# CHIP_tzatziffy_v8.net
KiCad netlist of a schematic drawn in EAGLE
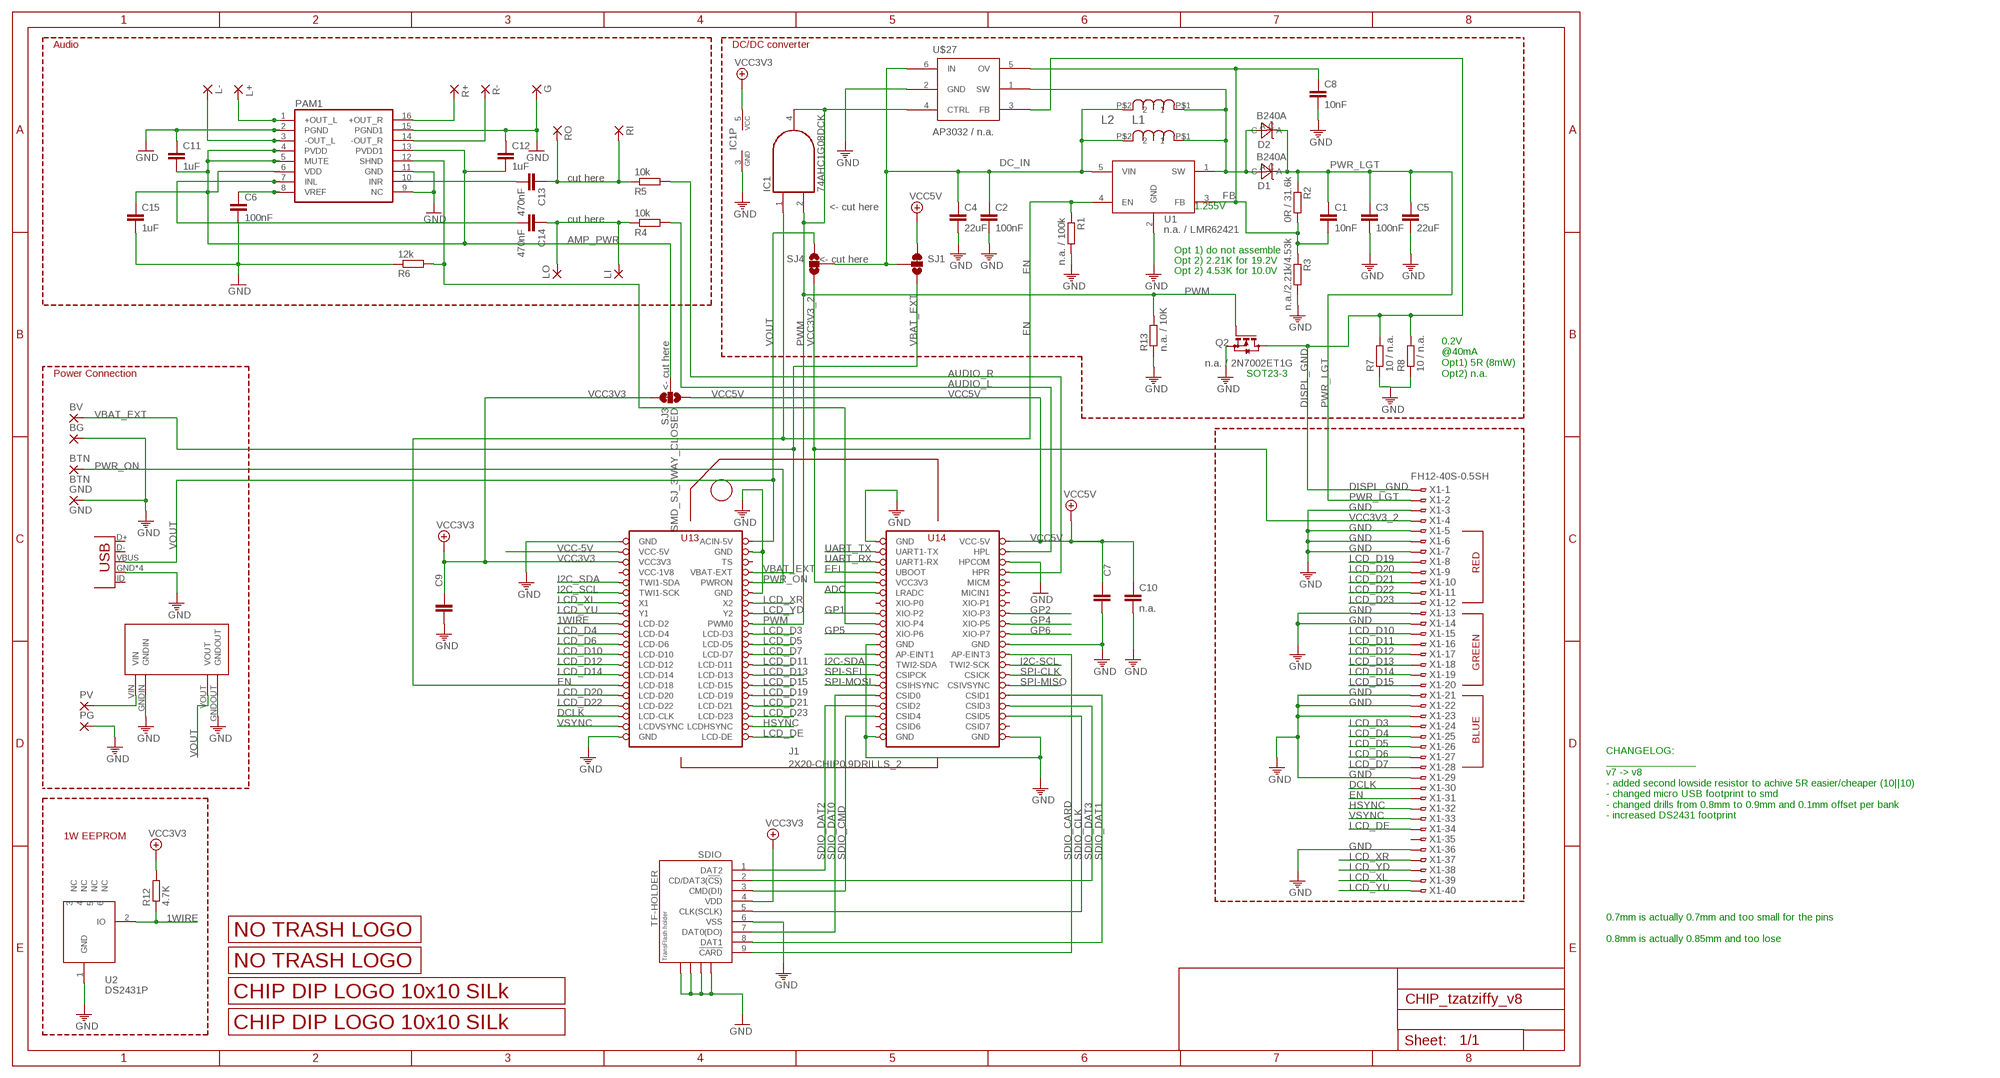
[diagram p0: schematic, sheet 1]

(export (version "E")
  (design (tool "Eeschema 10.0.6"))
  (components
    (comp (ref "BG")
      (value "1,6/0,8")
      (footprint "eagle-import:1,6_0,8")
      (libsource (lib "eagle-import") (part "1,6/0,8"))
    )
    (comp (ref "BTN")
      (value "BTN")
      (footprint "eagle-import:SMD1,27-2,54")
      (libsource (lib "eagle-import") (part "SMD2"))
    )
    (comp (ref "BV")
      (value "1,6/0,8")
      (footprint "eagle-import:1,6_0,8")
      (libsource (lib "eagle-import") (part "1,6/0,8"))
    )
    (comp (ref "C1")
      (value "10nF")
      (footprint "eagle-import:C0805")
      (libsource (lib "eagle-import") (part "C-EUC0805"))
    )
    (comp (ref "C2")
      (value "100nF")
      (footprint "eagle-import:C0805")
      (libsource (lib "eagle-import") (part "C-EUC0805"))
    )
    (comp (ref "C3")
      (value "100nF")
      (footprint "eagle-import:C0805")
      (libsource (lib "eagle-import") (part "C-EUC0805"))
    )
    (comp (ref "C4")
      (value "22uF")
      (footprint "eagle-import:C1206")
      (libsource (lib "eagle-import") (part "C-EUC1206"))
    )
    (comp (ref "C5")
      (value "22uF")
      (footprint "eagle-import:C1206")
      (libsource (lib "eagle-import") (part "C-EUC1206"))
    )
    (comp (ref "C6")
      (value "100nF")
      (footprint "eagle-import:C0805")
      (libsource (lib "eagle-import") (part "C-EUC0805"))
    )
    (comp (ref "C7")
      (value "n.a.")
      (footprint "eagle-import:C0805")
      (libsource (lib "eagle-import") (part "C-EUC0805"))
    )
    (comp (ref "C8")
      (value "10nF")
      (footprint "eagle-import:C0805")
      (libsource (lib "eagle-import") (part "C-EUC0805"))
    )
    (comp (ref "C9")
      (value "n.a.")
      (footprint "eagle-import:C0805")
      (libsource (lib "eagle-import") (part "C-EUC0805"))
    )
    (comp (ref "C10")
      (value "n.a.")
      (footprint "eagle-import:C0805")
      (libsource (lib "eagle-import") (part "C-EUC0805"))
    )
    (comp (ref "C11")
      (value "1uF")
      (footprint "eagle-import:C0805")
      (libsource (lib "eagle-import") (part "C-EUC0805"))
    )
    (comp (ref "C12")
      (value "1uF")
      (footprint "eagle-import:C0805")
      (libsource (lib "eagle-import") (part "C-EUC0805"))
    )
    (comp (ref "C13")
      (value "470nF")
      (footprint "eagle-import:C0805")
      (libsource (lib "eagle-import") (part "C-EUC0805"))
    )
    (comp (ref "C14")
      (value "470nF")
      (footprint "eagle-import:C0805")
      (libsource (lib "eagle-import") (part "C-EUC0805"))
    )
    (comp (ref "C15")
      (value "1uF")
      (footprint "eagle-import:C0805")
      (libsource (lib "eagle-import") (part "C-EUC0805"))
    )
    (comp (ref "D1")
      (value "B240A")
      (footprint "eagle-import:DO-214AC")
      (fields (field (name "MFG") "DIGIKEY") (field (name "VENDOR_PART_NUMBER") "B240A-13-F"))
      (libsource (lib "eagle-import") (part "DIODE_SCHTKY_B240"))
    )
    (comp (ref "D2")
      (value "B240A")
      (footprint "eagle-import:DO-214AC")
      (fields (field (name "MFG") "DIGIKEY") (field (name "VENDOR_PART_NUMBER") "B240A-13-F"))
      (libsource (lib "eagle-import") (part "DIODE_SCHTKY_B240"))
    )
    (comp (ref "G")
      (value "1,6/0,8")
      (footprint "eagle-import:1,6_0,8")
      (libsource (lib "eagle-import") (part "1,6/0,8"))
    )
    (comp (ref "GND")
      (value "GND")
      (footprint "eagle-import:SMD1,27-2,54")
      (libsource (lib "eagle-import") (part "SMD2"))
    )
    (comp (ref "IC1")
      (value "74AHC1G08DCK")
      (footprint "eagle-import:SC70-5")
      (libsource (lib "eagle-import") (part "741G08DCKAHC"))
    )
    (comp (ref "J1")
      (value "2X20-CHIP0.9DRILLS_2")
      (footprint "eagle-import:2X20CHIP_BANK_OFFSET_TH_0.9")
      (libsource (lib "eagle-import") (part "2X20-CHIP0.9DRILLS_2"))
    )
    (comp (ref "JP1")
      (value "USBMICRO_SMD")
      (footprint "eagle-import:USB-B-MICRO-SMD_V03")
      (libsource (lib "eagle-import") (part "USBMICRO_SMD"))
    )
    (comp (ref "L+")
      (value "1,6/0,8")
      (footprint "eagle-import:1,6_0,8")
      (libsource (lib "eagle-import") (part "1,6/0,8"))
    )
    (comp (ref "L-")
      (value "1,6/0,8")
      (footprint "eagle-import:1,6_0,8")
      (libsource (lib "eagle-import") (part "1,6/0,8"))
    )
    (comp (ref "L1")
      (value "SRN6045-100M")
      (footprint "eagle-import:SRN6045")
      (fields (field (name "MFG") "DIGIKEY"))
      (libsource (lib "eagle-import") (part "SRN6045-100M"))
    )
    (comp (ref "L2")
      (value "SRN6045-100M")
      (footprint "eagle-import:SRN6045")
      (fields (field (name "MFG") "DIGIKEY"))
      (libsource (lib "eagle-import") (part "SRN6045-100M"))
    )
    (comp (ref "LI")
      (value "1,6/0,8")
      (footprint "eagle-import:1,6_0,8")
      (libsource (lib "eagle-import") (part "1,6/0,8"))
    )
    (comp (ref "LO")
      (value "1,6/0,8")
      (footprint "eagle-import:1,6_0,8")
      (libsource (lib "eagle-import") (part "1,6/0,8"))
    )
    (comp (ref "PAM1")
      (value "PAM8403")
      (footprint "eagle-import:SOP-16")
      (libsource (lib "eagle-import") (part "PAM8403"))
    )
    (comp (ref "PG")
      (value "1,6/0,8")
      (footprint "eagle-import:1,6_0,8")
      (libsource (lib "eagle-import") (part "1,6/0,8"))
    )
    (comp (ref "PV")
      (value "1,6/0,8")
      (footprint "eagle-import:1,6_0,8")
      (libsource (lib "eagle-import") (part "1,6/0,8"))
    )
    (comp (ref "Q2")
      (value "n.a. / 2N7002ET1G")
      (footprint "eagle-import:SOT23")
      (libsource (lib "eagle-import") (part "BSS123"))
    )
    (comp (ref "R+")
      (value "1,6/0,8")
      (footprint "eagle-import:1,6_0,8")
      (libsource (lib "eagle-import") (part "1,6/0,8"))
    )
    (comp (ref "R-")
      (value "1,6/0,8")
      (footprint "eagle-import:1,6_0,8")
      (libsource (lib "eagle-import") (part "1,6/0,8"))
    )
    (comp (ref "R1")
      (value "n.a. / 100k")
      (footprint "eagle-import:M0805")
      (libsource (lib "eagle-import") (part "R-EU_M0805"))
    )
    (comp (ref "R2")
      (value "0R / 31.6k")
      (footprint "eagle-import:M0805")
      (libsource (lib "eagle-import") (part "R-EU_M0805"))
    )
    (comp (ref "R3")
      (value "n.a./2.21k/4.53k")
      (footprint "eagle-import:M0805")
      (libsource (lib "eagle-import") (part "R-EU_M0805"))
    )
    (comp (ref "R4")
      (value "10k")
      (footprint "eagle-import:R0805")
      (libsource (lib "eagle-import") (part "R-EU_R0805"))
    )
    (comp (ref "R5")
      (value "10k")
      (footprint "eagle-import:R0805")
      (libsource (lib "eagle-import") (part "R-EU_R0805"))
    )
    (comp (ref "R6")
      (value "12k")
      (footprint "eagle-import:R0805")
      (libsource (lib "eagle-import") (part "R-EU_R0805"))
    )
    (comp (ref "R7")
      (value "10 / n.a.")
      (footprint "eagle-import:M0805")
      (libsource (lib "eagle-import") (part "R-EU_M0805"))
    )
    (comp (ref "R8")
      (value "10 / n.a.")
      (footprint "eagle-import:M0805")
      (libsource (lib "eagle-import") (part "R-EU_M0805"))
    )
    (comp (ref "R12")
      (value "4.7K")
      (footprint "eagle-import:M0805")
      (libsource (lib "eagle-import") (part "R-EU_M0805"))
    )
    (comp (ref "R13")
      (value "n.a. / 10K")
      (footprint "eagle-import:M0805")
      (libsource (lib "eagle-import") (part "R-EU_M0805"))
    )
    (comp (ref "RI")
      (value "1,6/0,8")
      (footprint "eagle-import:1,6_0,8")
      (libsource (lib "eagle-import") (part "1,6/0,8"))
    )
    (comp (ref "RO")
      (value "1,6/0,8")
      (footprint "eagle-import:1,6_0,8")
      (libsource (lib "eagle-import") (part "1,6/0,8"))
    )
    (comp (ref "SDIO")
      (value "TF-HOLDER")
      (footprint "eagle-import:TF-PULL")
      (libsource (lib "eagle-import") (part "TF-HOLDER"))
    )
    (comp (ref "SJ1")
      (value "SMD_SJ_3WAY_CLOSED")
      (footprint "eagle-import:SMD_SJ_3WAY_CLOSED")
      (libsource (lib "eagle-import") (part "SMD_SJ_3WAY_CLOSED"))
    )
    (comp (ref "SJ3")
      (value "SMD_SJ_3WAY_CLOSED")
      (footprint "eagle-import:SMD_SJ_3WAY_CLOSED")
      (libsource (lib "eagle-import") (part "SMD_SJ_3WAY_CLOSED"))
    )
    (comp (ref "SJ4")
      (value "SMD_SJ_3WAY_OPENT")
      (footprint "eagle-import:SMD_SJ_3WAY_OPEN")
      (libsource (lib "eagle-import") (part "SMD_SJ_3WAY_OPENT"))
    )
    (comp (ref "U$2")
      (value "LOGO_10X10_SILK")
      (footprint "eagle-import:LOGO2_10X10_SILK")
      (libsource (lib "eagle-import") (part "LOGO_10X10_SILK"))
    )
    (comp (ref "U$3")
      (value "LOGO_NO_TRASHROHS")
      (footprint "eagle-import:LOGO_ROHS_SYM")
      (libsource (lib "eagle-import") (part "LOGO_NO_TRASHROHS"))
    )
    (comp (ref "U$4")
      (value "LOGO_NO_TRASHNO_TRASH")
      (footprint "eagle-import:LOGO_ROHS_NO_TRASH")
      (libsource (lib "eagle-import") (part "LOGO_NO_TRASHNO_TRASH"))
    )
    (comp (ref "U$5")
      (value "LOGO_10X10_SILK")
      (footprint "eagle-import:LOGO2_10X10_SILK")
      (libsource (lib "eagle-import") (part "LOGO_10X10_SILK"))
    )
    (comp (ref "U$10")
      (value "MP1584EN_FRAMELESS")
      (footprint "eagle-import:MP1584EN_FRAMELESS")
      (libsource (lib "eagle-import") (part "MP1584EN_FRAMELESS"))
    )
    (comp (ref "U$27")
      (value "AP3032 / n.a.")
      (footprint "eagle-import:SOT23-6")
      (libsource (lib "eagle-import") (part "AP3032"))
    )
    (comp (ref "U1")
      (value "n.a. / LMR62421")
      (footprint "eagle-import:SOT23-5")
      (fields (field (name "MFG") "DIGIKEY") (field (name "VENDOR_PART_NUMBER") "LMR62421XMFE/NOPB"))
      (libsource (lib "eagle-import") (part "LMR62421"))
    )
    (comp (ref "U2")
      (value "DS2431P")
      (footprint "eagle-import:TSOC6")
      (fields (field (name "MFG") "DIGIKEY") (field (name "VENDOR_PART_NUMBER") "DS2431P+T&R"))
      (libsource (lib "eagle-import") (part "DS2431P"))
    )
    (comp (ref "X1")
      (value "FH12-40S-0.5SH")
      (footprint "eagle-import:FH12-40S-0.5SH")
      (fields (field (name "MFG") "DIGIKEY") (field (name "VENDOR_PART_NUMBER") "FH12-40S-0.5SH(55)"))
      (libsource (lib "eagle-import") (part "FH12-40S-0.5SH"))
    )
  )
  (nets
    (net (code "1") (name "/1WIRE") (class "Default")
      (node (ref "J1") (pin "LCD-D2") (pinfunction "LCD-D2_LCD-D2") (pintype "passive"))
      (node (ref "R12") (pin "1") (pinfunction "1_1") (pintype "passive"))
      (node (ref "U2") (pin "2") (pinfunction "IO_2") (pintype "bidirectional"))
    )
    (net (code "2") (name "/ADC") (class "Default")
      (node (ref "J1") (pin "LRADC") (pinfunction "LRADC_LRADC") (pintype "passive"))
    )
    (net (code "3") (name "/AMP_PWR") (class "Default")
      (node (ref "C11") (pin "2") (pinfunction "2_2") (pintype "passive"))
      (node (ref "C12") (pin "2") (pinfunction "2_2") (pintype "passive"))
      (node (ref "C15") (pin "1") (pinfunction "1_1") (pintype "passive"))
      (node (ref "PAM1") (pin "13") (pinfunction "PVDD1_13") (pintype "output"))
      (node (ref "PAM1") (pin "4") (pinfunction "PVDD_4") (pintype "input"))
      (node (ref "PAM1") (pin "5") (pinfunction "MUTE_5") (pintype "input"))
      (node (ref "PAM1") (pin "6") (pinfunction "VDD_6") (pintype "input"))
      (node (ref "SJ3") (pin "2") (pinfunction "2_2") (pintype "passive"))
    )
    (net (code "4") (name "/AUDIO_L") (class "Default")
      (node (ref "J1") (pin "HPL") (pinfunction "HPL_HPL") (pintype "passive"))
      (node (ref "R4") (pin "2") (pinfunction "2_2") (pintype "passive"))
    )
    (net (code "5") (name "/AUDIO_R") (class "Default")
      (node (ref "J1") (pin "HPR") (pinfunction "HPR_HPR") (pintype "passive"))
      (node (ref "R5") (pin "2") (pinfunction "2_2") (pintype "passive"))
    )
    (net (code "6") (name "/DCLK") (class "Default")
      (node (ref "J1") (pin "LCD-CLK") (pinfunction "LCD-CLK_LCD-CLK") (pintype "passive"))
      (node (ref "X1") (pin "30") (pinfunction "1_30") (pintype "passive"))
    )
    (net (code "7") (name "/DC_IN") (class "Default")
      (node (ref "C2") (pin "1") (pinfunction "1_1") (pintype "passive"))
      (node (ref "C4") (pin "1") (pinfunction "1_1") (pintype "passive"))
      (node (ref "L1") (pin "P$2") (pinfunction "2_P$2") (pintype "passive"))
      (node (ref "L2") (pin "P$2") (pinfunction "2_P$2") (pintype "passive"))
      (node (ref "SJ1") (pin "2") (pinfunction "2_2") (pintype "passive"))
      (node (ref "SJ4") (pin "2") (pinfunction "2_2") (pintype "passive"))
      (node (ref "U$27") (pin "6") (pinfunction "IN_6") (pintype "power_in"))
      (node (ref "U1") (pin "5") (pinfunction "VIN_5") (pintype "bidirectional"))
    )
    (net (code "8") (name "/DISPL_GND") (class "Default")
      (node (ref "Q2") (pin "3") (pinfunction "D_3") (pintype "passive"))
      (node (ref "R7") (pin "2") (pinfunction "2_2") (pintype "passive"))
      (node (ref "R8") (pin "2") (pinfunction "2_2") (pintype "passive"))
      (node (ref "U$27") (pin "3") (pinfunction "FB_3") (pintype "passive"))
      (node (ref "X1") (pin "1") (pinfunction "1_1") (pintype "passive"))
    )
    (net (code "9") (name "/EN") (class "Default")
      (node (ref "IC1") (pin "1") (pinfunction "I0_1") (pintype "input"))
      (node (ref "J1") (pin "LCD-D18") (pinfunction "LCD-D18_LCD-D18") (pintype "passive"))
      (node (ref "R1") (pin "1") (pinfunction "1_1") (pintype "passive"))
      (node (ref "U1") (pin "4") (pinfunction "EN_4") (pintype "bidirectional"))
      (node (ref "X1") (pin "31") (pinfunction "1_31") (pintype "passive"))
    )
    (net (code "10") (name "/FB") (class "Default")
      (node (ref "C1") (pin "2") (pinfunction "2_2") (pintype "passive"))
      (node (ref "C8") (pin "1") (pinfunction "1_1") (pintype "passive"))
      (node (ref "R2") (pin "2") (pinfunction "2_2") (pintype "passive"))
      (node (ref "R3") (pin "1") (pinfunction "1_1") (pintype "passive"))
      (node (ref "U$27") (pin "5") (pinfunction "OV_5") (pintype "power_in"))
      (node (ref "U1") (pin "3") (pinfunction "FB_3") (pintype "bidirectional"))
    )
    (net (code "11") (name "/FEL") (class "Default")
      (node (ref "J1") (pin "FEL") (pinfunction "UBOOT_FEL") (pintype "passive"))
    )
    (net (code "12") (name "/GP1") (class "Default")
      (node (ref "J1") (pin "XIO-P2") (pinfunction "XIO-P2_XIO-P2") (pintype "passive"))
    )
    (net (code "13") (name "/GP2") (class "Default")
      (node (ref "J1") (pin "XIO-P3") (pinfunction "XIO-P3_XIO-P3") (pintype "passive"))
    )
    (net (code "14") (name "/GP4") (class "Default")
      (node (ref "J1") (pin "XIO-P5") (pinfunction "XIO-P5_XIO-P5") (pintype "passive"))
    )
    (net (code "15") (name "/GP5") (class "Default")
      (node (ref "J1") (pin "XIO-P6") (pinfunction "XIO-P6_XIO-P6") (pintype "passive"))
    )
    (net (code "16") (name "/GP6") (class "Default")
      (node (ref "J1") (pin "XIO-P7") (pinfunction "XIO-P7_XIO-P7") (pintype "passive"))
    )
    (net (code "17") (name "/HSYNC") (class "Default")
      (node (ref "J1") (pin "LCD-HSYNC") (pinfunction "LCDHSYNC_LCD-HSYNC") (pintype "passive"))
      (node (ref "X1") (pin "32") (pinfunction "1_32") (pintype "passive"))
    )
    (net (code "18") (name "/I2C-SCL") (class "Default")
      (node (ref "J1") (pin "TWI2-SCK") (pinfunction "TWI2-SCK_TWI2-SCK") (pintype "passive"))
    )
    (net (code "19") (name "/I2C-SDA") (class "Default")
      (node (ref "J1") (pin "TWI2-SDA") (pinfunction "TWI2-SDA_TWI2-SDA") (pintype "passive"))
    )
    (net (code "20") (name "/I2C_SCL") (class "Default")
      (node (ref "J1") (pin "TWI1-SCK") (pinfunction "TWI1-SCK_TWI1-SCK") (pintype "passive"))
    )
    (net (code "21") (name "/I2C_SDA") (class "Default")
      (node (ref "J1") (pin "TWI1-SDA") (pinfunction "TWI1-SDA_TWI1-SDA") (pintype "passive"))
    )
    (net (code "22") (name "/LCD_D3") (class "Default")
      (node (ref "J1") (pin "LCD-D3") (pinfunction "LCD-D3_LCD-D3") (pintype "passive"))
      (node (ref "X1") (pin "24") (pinfunction "1_24") (pintype "passive"))
    )
    (net (code "23") (name "/LCD_D4") (class "Default")
      (node (ref "J1") (pin "LCD-D4") (pinfunction "LCD-D4_LCD-D4") (pintype "passive"))
      (node (ref "X1") (pin "25") (pinfunction "1_25") (pintype "passive"))
    )
    (net (code "24") (name "/LCD_D5") (class "Default")
      (node (ref "J1") (pin "LCD-D5") (pinfunction "LCD-D5_LCD-D5") (pintype "passive"))
      (node (ref "X1") (pin "26") (pinfunction "1_26") (pintype "passive"))
    )
    (net (code "25") (name "/LCD_D6") (class "Default")
      (node (ref "J1") (pin "LCD-D6") (pinfunction "LCD-D6_LCD-D6") (pintype "passive"))
      (node (ref "X1") (pin "27") (pinfunction "1_27") (pintype "passive"))
    )
    (net (code "26") (name "/LCD_D7") (class "Default")
      (node (ref "J1") (pin "LCD-D7") (pinfunction "LCD-D7_LCD-D7") (pintype "passive"))
      (node (ref "X1") (pin "28") (pinfunction "1_28") (pintype "passive"))
    )
    (net (code "27") (name "/LCD_D10") (class "Default")
      (node (ref "J1") (pin "LCD-D10") (pinfunction "LCD-D10_LCD-D10") (pintype "passive"))
      (node (ref "X1") (pin "15") (pinfunction "1_15") (pintype "passive"))
    )
    (net (code "28") (name "/LCD_D11") (class "Default")
      (node (ref "J1") (pin "LCD-D11") (pinfunction "LCD-D11_LCD-D11") (pintype "passive"))
      (node (ref "X1") (pin "16") (pinfunction "1_16") (pintype "passive"))
    )
    (net (code "29") (name "/LCD_D12") (class "Default")
      (node (ref "J1") (pin "LCD-D12") (pinfunction "LCD-D12_LCD-D12") (pintype "passive"))
      (node (ref "X1") (pin "17") (pinfunction "1_17") (pintype "passive"))
    )
    (net (code "30") (name "/LCD_D13") (class "Default")
      (node (ref "J1") (pin "LCD-D13") (pinfunction "LCD-D13_LCD-D13") (pintype "passive"))
      (node (ref "X1") (pin "18") (pinfunction "1_18") (pintype "passive"))
    )
    (net (code "31") (name "/LCD_D14") (class "Default")
      (node (ref "J1") (pin "LCD-D14") (pinfunction "LCD-D14_LCD-D14") (pintype "passive"))
      (node (ref "X1") (pin "19") (pinfunction "1_19") (pintype "passive"))
    )
    (net (code "32") (name "/LCD_D15") (class "Default")
      (node (ref "J1") (pin "LCD-D15") (pinfunction "LCD-D15_LCD-D15") (pintype "passive"))
      (node (ref "X1") (pin "20") (pinfunction "1_20") (pintype "passive"))
    )
    (net (code "33") (name "/LCD_D19") (class "Default")
      (node (ref "J1") (pin "LCD-D19") (pinfunction "LCD-D19_LCD-D19") (pintype "passive"))
      (node (ref "X1") (pin "8") (pinfunction "1_8") (pintype "passive"))
    )
    (net (code "34") (name "/LCD_D20") (class "Default")
      (node (ref "J1") (pin "LCD-D20") (pinfunction "LCD-D20_LCD-D20") (pintype "passive"))
      (node (ref "X1") (pin "9") (pinfunction "1_9") (pintype "passive"))
    )
    (net (code "35") (name "/LCD_D21") (class "Default")
      (node (ref "J1") (pin "LCD-D21") (pinfunction "LCD-D21_LCD-D21") (pintype "passive"))
      (node (ref "X1") (pin "10") (pinfunction "1_10") (pintype "passive"))
    )
    (net (code "36") (name "/LCD_D22") (class "Default")
      (node (ref "J1") (pin "LCD-D22") (pinfunction "LCD-D22_LCD-D22") (pintype "passive"))
      (node (ref "X1") (pin "11") (pinfunction "1_11") (pintype "passive"))
    )
    (net (code "37") (name "/LCD_D23") (class "Default")
      (node (ref "J1") (pin "LCD-D23") (pinfunction "LCD-D23_LCD-D23") (pintype "passive"))
      (node (ref "X1") (pin "12") (pinfunction "1_12") (pintype "passive"))
    )
    (net (code "38") (name "/LCD_DE") (class "Default")
      (node (ref "J1") (pin "LCD-DE") (pinfunction "LCD-DE_LCD-DE") (pintype "passive"))
      (node (ref "X1") (pin "34") (pinfunction "1_34") (pintype "passive"))
    )
    (net (code "39") (name "/LCD_XL") (class "Default")
      (node (ref "J1") (pin "X1") (pinfunction "X1_X1") (pintype "passive"))
      (node (ref "X1") (pin "39") (pinfunction "1_39") (pintype "passive"))
    )
    (net (code "40") (name "/LCD_XR") (class "Default")
      (node (ref "J1") (pin "X2") (pinfunction "X2_X2") (pintype "passive"))
      (node (ref "X1") (pin "37") (pinfunction "1_37") (pintype "passive"))
    )
    (net (code "41") (name "/LCD_YD") (class "Default")
      (node (ref "J1") (pin "Y2") (pinfunction "Y2_Y2") (pintype "passive"))
      (node (ref "X1") (pin "38") (pinfunction "1_38") (pintype "passive"))
    )
    (net (code "42") (name "/LCD_YU") (class "Default")
      (node (ref "J1") (pin "Y1") (pinfunction "Y1_Y1") (pintype "passive"))
      (node (ref "X1") (pin "40") (pinfunction "1_40") (pintype "passive"))
    )
    (net (code "43") (name "/PWM") (class "Default")
      (node (ref "IC1") (pin "2") (pinfunction "I1_2") (pintype "input"))
      (node (ref "IC1") (pin "4") (pinfunction "O_4") (pintype "output"))
      (node (ref "J1") (pin "PWM0") (pinfunction "PWM0_PWM0") (pintype "passive"))
      (node (ref "Q2") (pin "1") (pinfunction "G_1") (pintype "passive"))
      (node (ref "R13") (pin "2") (pinfunction "2_2") (pintype "passive"))
      (node (ref "U$27") (pin "4") (pinfunction "CTRL_4") (pintype "input"))
    )
    (net (code "44") (name "/PWR_LGT") (class "Default")
      (node (ref "C1") (pin "1") (pinfunction "1_1") (pintype "passive"))
      (node (ref "C3") (pin "1") (pinfunction "1_1") (pintype "passive"))
      (node (ref "C5") (pin "1") (pinfunction "1_1") (pintype "passive"))
      (node (ref "D1") (pin "C") (pinfunction "C_C") (pintype "bidirectional"))
      (node (ref "D2") (pin "C") (pinfunction "C_C") (pintype "bidirectional"))
      (node (ref "R2") (pin "1") (pinfunction "1_1") (pintype "passive"))
      (node (ref "X1") (pin "2") (pinfunction "1_2") (pintype "passive"))
    )
    (net (code "45") (name "/PWR_ON") (class "Default")
      (node (ref "BTN") (pin "1") (pinfunction "P_1") (pintype "passive"))
      (node (ref "J1") (pin "PWRON") (pinfunction "PWRON_PWRON") (pintype "passive"))
    )
    (net (code "46") (name "/SDIO_CARD") (class "Default")
      (node (ref "J1") (pin "AP-EINT3") (pinfunction "AP-EINT3_AP-EINT3") (pintype "passive"))
      (node (ref "SDIO") (pin "9") (pinfunction "~{CARD}_9") (pintype "passive"))
    )
    (net (code "47") (name "/SDIO_CLK") (class "Default")
      (node (ref "J1") (pin "CSID5") (pinfunction "CSID5_CSID5") (pintype "passive"))
      (node (ref "SDIO") (pin "5") (pinfunction "CLK(SCLK)_5") (pintype "input"))
    )
    (net (code "48") (name "/SDIO_CMD") (class "Default")
      (node (ref "J1") (pin "CSID4") (pinfunction "CSID4_CSID4") (pintype "passive"))
      (node (ref "SDIO") (pin "3") (pinfunction "CMD(DI)_3") (pintype "bidirectional"))
    )
    (net (code "49") (name "/SDIO_DAT0") (class "Default")
      (node (ref "J1") (pin "CSID0") (pinfunction "CSID0_CSID0") (pintype "passive"))
      (node (ref "SDIO") (pin "7") (pinfunction "DAT0(DO)_7") (pintype "bidirectional"))
    )
    (net (code "50") (name "/SDIO_DAT1") (class "Default")
      (node (ref "J1") (pin "CSID1") (pinfunction "CSID1_CSID1") (pintype "passive"))
      (node (ref "SDIO") (pin "8") (pinfunction "DAT1_8") (pintype "bidirectional"))
    )
    (net (code "51") (name "/SDIO_DAT2") (class "Default")
      (node (ref "J1") (pin "CSID2") (pinfunction "CSID2_CSID2") (pintype "passive"))
      (node (ref "SDIO") (pin "1") (pinfunction "DAT2_1") (pintype "bidirectional"))
    )
    (net (code "52") (name "/SDIO_DAT3") (class "Default")
      (node (ref "J1") (pin "CSID3") (pinfunction "CSID3_CSID3") (pintype "passive"))
      (node (ref "SDIO") (pin "2") (pinfunction "CD/DAT3(~{CS})_2") (pintype "bidirectional"))
    )
    (net (code "53") (name "/SPI-CLK") (class "Default")
      (node (ref "J1") (pin "CSICK") (pinfunction "CSICK_CSICK") (pintype "passive"))
    )
    (net (code "54") (name "/SPI-MISO") (class "Default")
      (node (ref "J1") (pin "CSIVSYNC") (pinfunction "CSIVSYNC_CSIVSYNC") (pintype "passive"))
    )
    (net (code "55") (name "/SPI-MOSI") (class "Default")
      (node (ref "J1") (pin "CSIHSYNC") (pinfunction "CSIHSYNC_CSIHSYNC") (pintype "passive"))
    )
    (net (code "56") (name "/SPI-SEL") (class "Default")
      (node (ref "J1") (pin "CSIPCK") (pinfunction "CSIPCK_CSIPCK") (pintype "passive"))
    )
    (net (code "57") (name "/UART_RX") (class "Default")
      (node (ref "J1") (pin "UART1-RX") (pinfunction "UART1-RX_UART1-RX") (pintype "passive"))
    )
    (net (code "58") (name "/UART_TX") (class "Default")
      (node (ref "J1") (pin "UART1-TX") (pinfunction "UART1-TX_UART1-TX") (pintype "passive"))
    )
    (net (code "59") (name "/VBAT_EXT") (class "Default")
      (node (ref "BV") (pin "1") (pinfunction "P_1") (pintype "passive"))
      (node (ref "J1") (pin "BAT") (pinfunction "VBAT-EXT_BAT") (pintype "passive"))
      (node (ref "SJ1") (pin "3") (pinfunction "3_3") (pintype "passive"))
    )
    (net (code "60") (name "/VCC-1V8") (class "Default")
      (node (ref "J1") (pin "VCC1V8") (pinfunction "VCC-1V8_VCC1V8") (pintype "power_in"))
    )
    (net (code "61") (name "/VCC-5V") (class "Default")
      (node (ref "J1") (pin "VCC5V@0") (pinfunction "VCC-5V_VCC5V@0") (pintype "power_in"))
    )
    (net (code "62") (name "/VCC3V3_2") (class "Default")
      (node (ref "J1") (pin "VCC3V3@1") (pinfunction "VCC3V3_VCC3V3@1") (pintype "power_in"))
      (node (ref "SJ4") (pin "3") (pinfunction "3_3") (pintype "passive"))
      (node (ref "X1") (pin "4") (pinfunction "1_4") (pintype "passive"))
    )
    (net (code "63") (name "/VOUT") (class "Default")
      (node (ref "J1") (pin "CHG-IN") (pinfunction "ACIN-5V_CHG-IN") (pintype "passive"))
      (node (ref "JP1") (pin "VBUS") (pinfunction "VBUS_VBUS") (pintype "bidirectional"))
      (node (ref "SJ4") (pin "1") (pinfunction "1_1") (pintype "passive"))
      (node (ref "U$10") (pin "VOUT") (pinfunction "VOUT_VOUT") (pintype "power_in"))
    )
    (net (code "64") (name "/VSYNC") (class "Default")
      (node (ref "J1") (pin "LCD-VSYNC") (pinfunction "LCDVSYNC_LCD-VSYNC") (pintype "passive"))
      (node (ref "X1") (pin "33") (pinfunction "1_33") (pintype "passive"))
    )
    (net (code "65") (name "GND") (class "Default")
      (node (ref "BG") (pin "1") (pinfunction "P_1") (pintype "passive"))
      (node (ref "C10") (pin "2") (pinfunction "2_2") (pintype "passive"))
      (node (ref "C11") (pin "1") (pinfunction "1_1") (pintype "passive"))
      (node (ref "C12") (pin "1") (pinfunction "1_1") (pintype "passive"))
      (node (ref "C15") (pin "2") (pinfunction "2_2") (pintype "passive"))
      (node (ref "C2") (pin "2") (pinfunction "2_2") (pintype "passive"))
      (node (ref "C3") (pin "2") (pinfunction "2_2") (pintype "passive"))
      (node (ref "C4") (pin "2") (pinfunction "2_2") (pintype "passive"))
      (node (ref "C5") (pin "2") (pinfunction "2_2") (pintype "passive"))
      (node (ref "C6") (pin "2") (pinfunction "2_2") (pintype "passive"))
      (node (ref "C7") (pin "2") (pinfunction "2_2") (pintype "passive"))
      (node (ref "C8") (pin "2") (pinfunction "2_2") (pintype "passive"))
      (node (ref "C9") (pin "2") (pinfunction "2_2") (pintype "passive"))
      (node (ref "G") (pin "1") (pinfunction "P_1") (pintype "passive"))
      (node (ref "GND") (pin "1") (pinfunction "P_1") (pintype "passive"))
      (node (ref "IC1") (pin "3") (pinfunction "GND_3") (pintype "power_in"))
      (node (ref "J1") (pin "GND@1") (pinfunction "GND_GND@1") (pintype "power_in"))
      (node (ref "J1") (pin "GND@10") (pinfunction "GND_GND@10") (pintype "power_in"))
      (node (ref "J1") (pin "GND@2") (pinfunction "GND_GND@2") (pintype "power_in"))
      (node (ref "J1") (pin "GND@3") (pinfunction "GND_GND@3") (pintype "power_in"))
      (node (ref "J1") (pin "GND@4") (pinfunction "GND_GND@4") (pintype "power_in"))
      (node (ref "J1") (pin "GND@5") (pinfunction "GND_GND@5") (pintype "power_in"))
      (node (ref "J1") (pin "GND@6") (pinfunction "GND_GND@6") (pintype "power_in"))
      (node (ref "J1") (pin "GND@7") (pinfunction "GND_GND@7") (pintype "power_in"))
      (node (ref "J1") (pin "GND@8") (pinfunction "GND_GND@8") (pintype "power_in"))
      (node (ref "J1") (pin "HPCOM") (pinfunction "HPCOM_HPCOM") (pintype "passive"))
      (node (ref "JP1") (pin "GND") (pinfunction "GND_GND") (pintype "bidirectional"))
      (node (ref "JP1") (pin "SHIELD1") (pinfunction "GND_SHIELD1") (pintype "bidirectional"))
      (node (ref "JP1") (pin "SHIELD2") (pinfunction "GND_SHIELD2") (pintype "bidirectional"))
      (node (ref "JP1") (pin "SHIELD3") (pinfunction "GND_SHIELD3") (pintype "bidirectional"))
      (node (ref "PAM1") (pin "11") (pinfunction "GND_11") (pintype "output"))
      (node (ref "PAM1") (pin "15") (pinfunction "PGND1_15") (pintype "output"))
      (node (ref "PAM1") (pin "2") (pinfunction "PGND_2") (pintype "input"))
      (node (ref "PAM1") (pin "9") (pinfunction "NC_9") (pintype "output"))
      (node (ref "PG") (pin "1") (pinfunction "P_1") (pintype "passive"))
      (node (ref "Q2") (pin "2") (pinfunction "S_2") (pintype "passive"))
      (node (ref "R1") (pin "2") (pinfunction "2_2") (pintype "passive"))
      (node (ref "R13") (pin "1") (pinfunction "1_1") (pintype "passive"))
      (node (ref "R3") (pin "2") (pinfunction "2_2") (pintype "passive"))
      (node (ref "R6") (pin "1") (pinfunction "1_1") (pintype "passive"))
      (node (ref "R7") (pin "1") (pinfunction "1_1") (pintype "passive"))
      (node (ref "R8") (pin "1") (pinfunction "1_1") (pintype "passive"))
      (node (ref "SDIO") (pin "6") (pinfunction "VSS_6") (pintype "power_in"))
      (node (ref "SDIO") (pin "S1") (pinfunction "S1_S1") (pintype "passive"))
      (node (ref "SDIO") (pin "S2") (pinfunction "S2_S2") (pintype "passive"))
      (node (ref "SDIO") (pin "S3") (pinfunction "S3_S3") (pintype "passive"))
      (node (ref "SDIO") (pin "S4") (pinfunction "S4_S4") (pintype "passive"))
      (node (ref "U$10") (pin "GNDIN") (pinfunction "GNDIN_GNDIN") (pintype "power_in"))
      (node (ref "U$10") (pin "GNDOUT") (pinfunction "GNDOUT_GNDOUT") (pintype "power_in"))
      (node (ref "U$27") (pin "2") (pinfunction "GND_2") (pintype "power_in"))
      (node (ref "U1") (pin "2") (pinfunction "GND_2") (pintype "bidirectional"))
      (node (ref "U2") (pin "1") (pinfunction "GND_1") (pintype "bidirectional"))
      (node (ref "X1") (pin "13") (pinfunction "1_13") (pintype "passive"))
      (node (ref "X1") (pin "14") (pinfunction "1_14") (pintype "passive"))
      (node (ref "X1") (pin "21") (pinfunction "1_21") (pintype "passive"))
      (node (ref "X1") (pin "22") (pinfunction "1_22") (pintype "passive"))
      (node (ref "X1") (pin "23") (pinfunction "1_23") (pintype "passive"))
      (node (ref "X1") (pin "29") (pinfunction "1_29") (pintype "passive"))
      (node (ref "X1") (pin "3") (pinfunction "1_3") (pintype "passive"))
      (node (ref "X1") (pin "36") (pinfunction "1_36") (pintype "passive"))
      (node (ref "X1") (pin "5") (pinfunction "1_5") (pintype "passive"))
      (node (ref "X1") (pin "6") (pinfunction "1_6") (pintype "passive"))
      (node (ref "X1") (pin "7") (pinfunction "1_7") (pintype "passive"))
    )
    (net (code "66") (name "Net-(L+-P)") (class "Default")
      (node (ref "L+") (pin "1") (pinfunction "P_1") (pintype "passive"))
      (node (ref "PAM1") (pin "1") (pinfunction "+OUT_L_1") (pintype "input"))
    )
    (net (code "67") (name "Net-(L--P)") (class "Default")
      (node (ref "L-") (pin "1") (pinfunction "P_1") (pintype "passive"))
      (node (ref "PAM1") (pin "3") (pinfunction "-OUT_L_3") (pintype "input"))
    )
    (net (code "68") (name "Net-(L1-1)") (class "Default")
      (node (ref "D1") (pin "A") (pinfunction "A_A") (pintype "bidirectional"))
      (node (ref "D2") (pin "A") (pinfunction "A_A") (pintype "bidirectional"))
      (node (ref "L1") (pin "P$1") (pinfunction "1_P$1") (pintype "passive"))
      (node (ref "L2") (pin "P$1") (pinfunction "1_P$1") (pintype "passive"))
      (node (ref "U$27") (pin "1") (pinfunction "SW_1") (pintype "power_in"))
      (node (ref "U1") (pin "1") (pinfunction "SW_1") (pintype "bidirectional"))
    )
    (net (code "69") (name "Net-(LI-P)") (class "Default")
      (node (ref "C14") (pin "1") (pinfunction "1_1") (pintype "passive"))
      (node (ref "LI") (pin "1") (pinfunction "P_1") (pintype "passive"))
      (node (ref "LO") (pin "1") (pinfunction "P_1") (pintype "passive"))
      (node (ref "R4") (pin "1") (pinfunction "1_1") (pintype "passive"))
    )
    (net (code "70") (name "Net-(PAM1-+OUT_R)") (class "Default")
      (node (ref "PAM1") (pin "16") (pinfunction "+OUT_R_16") (pintype "output"))
      (node (ref "R+") (pin "1") (pinfunction "P_1") (pintype "passive"))
    )
    (net (code "71") (name "Net-(PAM1--OUT_R)") (class "Default")
      (node (ref "PAM1") (pin "14") (pinfunction "-OUT_R_14") (pintype "output"))
      (node (ref "R-") (pin "1") (pinfunction "P_1") (pintype "passive"))
    )
    (net (code "72") (name "Net-(PAM1-INL)") (class "Default")
      (node (ref "C14") (pin "2") (pinfunction "2_2") (pintype "passive"))
      (node (ref "PAM1") (pin "7") (pinfunction "INL_7") (pintype "input"))
    )
    (net (code "73") (name "Net-(PAM1-INR)") (class "Default")
      (node (ref "C13") (pin "2") (pinfunction "2_2") (pintype "passive"))
      (node (ref "PAM1") (pin "10") (pinfunction "INR_10") (pintype "output"))
    )
    (net (code "74") (name "Net-(PAM1-SHND)") (class "Default")
      (node (ref "J1") (pin "XIO-P4") (pinfunction "XIO-P4_XIO-P4") (pintype "passive"))
      (node (ref "PAM1") (pin "12") (pinfunction "SHND_12") (pintype "output"))
      (node (ref "R6") (pin "2") (pinfunction "2_2") (pintype "passive"))
    )
    (net (code "75") (name "Net-(PAM1-VREF)") (class "Default")
      (node (ref "C6") (pin "1") (pinfunction "1_1") (pintype "passive"))
      (node (ref "PAM1") (pin "8") (pinfunction "VREF_8") (pintype "input"))
    )
    (net (code "76") (name "Net-(PV-P)") (class "Default")
      (node (ref "PV") (pin "1") (pinfunction "P_1") (pintype "passive"))
      (node (ref "U$10") (pin "VIN") (pinfunction "VIN_VIN") (pintype "power_in"))
    )
    (net (code "77") (name "Net-(RI-P)") (class "Default")
      (node (ref "C13") (pin "1") (pinfunction "1_1") (pintype "passive"))
      (node (ref "R5") (pin "1") (pinfunction "1_1") (pintype "passive"))
      (node (ref "RI") (pin "1") (pinfunction "P_1") (pintype "passive"))
      (node (ref "RO") (pin "1") (pinfunction "P_1") (pintype "passive"))
    )
    (net (code "78") (name "VCC3V3") (class "Default")
      (node (ref "C9") (pin "1") (pinfunction "1_1") (pintype "passive"))
      (node (ref "IC1") (pin "5") (pinfunction "VCC_5") (pintype "power_in"))
      (node (ref "J1") (pin "VCC3V3") (pinfunction "VCC3V3_VCC3V3") (pintype "power_in"))
      (node (ref "R12") (pin "2") (pinfunction "2_2") (pintype "passive"))
      (node (ref "SDIO") (pin "4") (pinfunction "VDD_4") (pintype "power_in"))
      (node (ref "SJ3") (pin "1") (pinfunction "1_1") (pintype "passive"))
    )
    (net (code "79") (name "VCC5V") (class "Default")
      (node (ref "C10") (pin "1") (pinfunction "1_1") (pintype "passive"))
      (node (ref "C7") (pin "1") (pinfunction "1_1") (pintype "passive"))
      (node (ref "J1") (pin "VCC5V@1") (pinfunction "VCC-5V_VCC5V@1") (pintype "power_in"))
      (node (ref "SJ1") (pin "1") (pinfunction "1_1") (pintype "passive"))
      (node (ref "SJ3") (pin "3") (pinfunction "3_3") (pintype "passive"))
    )
    (net (code "80") (name "unconnected-(J1-PadAP-EINT1)") (class "Default")
      (node (ref "J1") (pin "AP-EINT1") (pinfunction "AP-EINT1_AP-EINT1") (pintype "passive"))
    )
    (net (code "81") (name "unconnected-(J1-PadCSID6)") (class "Default")
      (node (ref "J1") (pin "CSID6") (pinfunction "CSID6_CSID6") (pintype "passive"))
    )
    (net (code "82") (name "unconnected-(J1-PadCSID7)") (class "Default")
      (node (ref "J1") (pin "CSID7") (pinfunction "CSID7_CSID7") (pintype "passive"))
    )
    (net (code "83") (name "unconnected-(J1-PadMICIN1)") (class "Default")
      (node (ref "J1") (pin "MICIN1") (pinfunction "MICIN1_MICIN1") (pintype "passive"))
    )
    (net (code "84") (name "unconnected-(J1-PadMICM)") (class "Default")
      (node (ref "J1") (pin "MICM") (pinfunction "MICM_MICM") (pintype "passive"))
    )
    (net (code "85") (name "unconnected-(J1-PadTS)") (class "Default")
      (node (ref "J1") (pin "TS") (pinfunction "TS_TS") (pintype "passive"))
    )
    (net (code "86") (name "unconnected-(J1-PadXIO-P0)") (class "Default")
      (node (ref "J1") (pin "XIO-P0") (pinfunction "XIO-P0_XIO-P0") (pintype "passive"))
    )
    (net (code "87") (name "unconnected-(J1-PadXIO-P1)") (class "Default")
      (node (ref "J1") (pin "XIO-P1") (pinfunction "XIO-P1_XIO-P1") (pintype "passive"))
    )
    (net (code "88") (name "unconnected-(JP1-PadD+)") (class "Default")
      (node (ref "JP1") (pin "D+") (pinfunction "D+_D+") (pintype "bidirectional"))
    )
    (net (code "89") (name "unconnected-(JP1-PadD-)") (class "Default")
      (node (ref "JP1") (pin "D-") (pinfunction "D-_D-") (pintype "bidirectional"))
    )
    (net (code "90") (name "unconnected-(JP1-PadID)") (class "Default")
      (node (ref "JP1") (pin "ID") (pinfunction "ID_ID") (pintype "bidirectional"))
    )
    (net (code "91") (name "unconnected-(U2-NC-Pad3)") (class "Default")
      (node (ref "U2") (pin "3") (pinfunction "NC_3") (pintype "bidirectional"))
    )
    (net (code "92") (name "unconnected-(U2-NC-Pad4)") (class "Default")
      (node (ref "U2") (pin "4") (pinfunction "NC_4") (pintype "bidirectional"))
    )
    (net (code "93") (name "unconnected-(U2-NC-Pad5)") (class "Default")
      (node (ref "U2") (pin "5") (pinfunction "NC_5") (pintype "bidirectional"))
    )
    (net (code "94") (name "unconnected-(U2-NC-Pad6)") (class "Default")
      (node (ref "U2") (pin "6") (pinfunction "NC_6") (pintype "bidirectional"))
    )
    (net (code "95") (name "unconnected-(X1AC-1-Pad35)") (class "Default")
      (node (ref "X1") (pin "35") (pinfunction "1_35") (pintype "passive"))
    )
  )
)
